# GSB-S02-V00-Microcontroller.net
KiCad netlist of a schematic drawn in Altium Designer
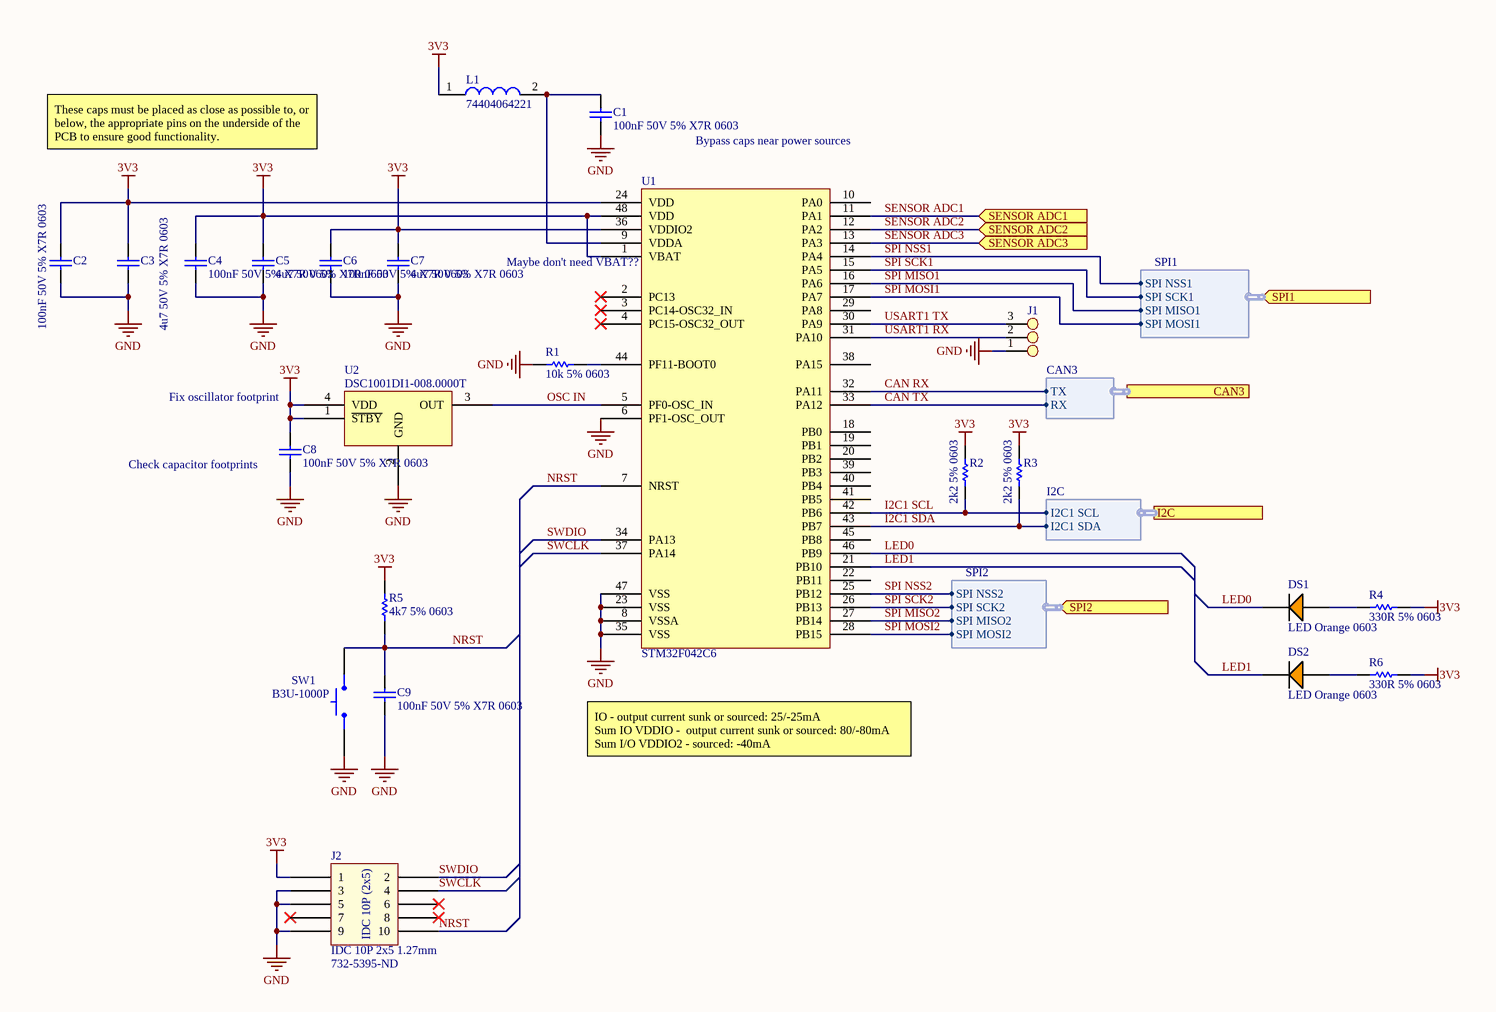
[diagram p0: GSB-S02-V00-Microcontroller.SchDoc]

(export (version "E")
  (design (tool "Eeschema 10.0.6"))
  (components
    (comp (ref "C1")
      (value "100nF 50V 5% X7R 0603")
      (footprint "Cap_Ceramic_0603")
      (description "Capacitor, Ceramic, SMD, 100nF, 50V, 5%, X7R, 0603")
      (libsource (lib "StandardCapacitors") (part "100nF 50V 5% X7R 0603"))
    )
    (comp (ref "C2")
      (value "100nF 50V 5% X7R 0603")
      (footprint "Cap_Ceramic_0603")
      (description "Capacitor, Ceramic, SMD, 100nF, 50V, 5%, X7R, 0603")
      (libsource (lib "StandardCapacitors") (part "100nF 50V 5% X7R 0603"))
    )
    (comp (ref "C3")
      (value "4u7 50V 5% X7R 0603")
      (footprint "Cap_Ceramic_0603")
      (description "Capacitor, Ceramic, SMD, 4u7, 50V, 5%, X7R, 0603")
      (libsource (lib "StandardCapacitors") (part "4u7 50V 5% X7R 0603"))
    )
    (comp (ref "C4")
      (value "100nF 50V 5% X7R 0603")
      (footprint "Cap_Ceramic_0603")
      (description "Capacitor, Ceramic, SMD, 100nF, 50V, 5%, X7R, 0603")
      (libsource (lib "StandardCapacitors") (part "100nF 50V 5% X7R 0603"))
    )
    (comp (ref "C5")
      (value "4u7 50V 5% X7R 0603")
      (footprint "Cap_Ceramic_0603")
      (description "Capacitor, Ceramic, SMD, 4u7, 50V, 5%, X7R, 0603")
      (libsource (lib "StandardCapacitors") (part "4u7 50V 5% X7R 0603"))
    )
    (comp (ref "C6")
      (value "100nF 50V 5% X7R 0603")
      (footprint "Cap_Ceramic_0603")
      (description "Capacitor, Ceramic, SMD, 100nF, 50V, 5%, X7R, 0603")
      (libsource (lib "StandardCapacitors") (part "100nF 50V 5% X7R 0603"))
    )
    (comp (ref "C7")
      (value "4u7 50V 5% X7R 0603")
      (footprint "Cap_Ceramic_0603")
      (description "Capacitor, Ceramic, SMD, 4u7, 50V, 5%, X7R, 0603")
      (libsource (lib "StandardCapacitors") (part "4u7 50V 5% X7R 0603"))
    )
    (comp (ref "C8")
      (value "100nF 50V 5% X7R 0603")
      (footprint "Cap_Ceramic_0603")
      (description "Capacitor, Ceramic, SMD, 100nF, 50V, 5%, X7R, 0603")
      (libsource (lib "StandardCapacitors") (part "100nF 50V 5% X7R 0603"))
    )
    (comp (ref "C9")
      (value "100nF 50V 5% X7R 0603")
      (footprint "Cap_Ceramic_0603")
      (description "Capacitor, Ceramic, SMD, 100nF, 50V, 5%, X7R, 0603")
      (libsource (lib "StandardCapacitors") (part "100nF 50V 5% X7R 0603"))
    )
    (comp (ref "DS1")
      (value "LED Orange 0603")
      (footprint "LED ORANGE 0603")
      (libsource (lib "QUTMS_LEDLibrary") (part "LED Orange 0603"))
    )
    (comp (ref "DS2")
      (value "LED Orange 0603")
      (footprint "LED ORANGE 0603")
      (libsource (lib "QUTMS_LEDLibrary") (part "LED Orange 0603"))
    )
    (comp (ref "J1")
      (value "Jumper 3Way Pins")
      (footprint "Jumper_3Way_Pin")
      (description "Jumper 3Way Side Pins")
      (libsource (lib "QUTMS_JumperLibrary") (part "Jumper 3Way Side Pins"))
    )
    (comp (ref "J2")
      (value "IDC 10P 2x5 1.27mm")
      (footprint "IDC 1.27MM 10P")
      (libsource (lib "IDCConnectors") (part "IDC 10P 2x5 1.27mm"))
    )
    (comp (ref "L1")
      (value "74404064221")
      (footprint "Inductor_6x6mm")
      (description "FIXED IND 220UH 660MA 850 MOHM")
      (libsource (lib "QUTMS_InductorLibrary") (part "74404064221"))
    )
    (comp (ref "R1")
      (value "10k 5% 0603")
      (footprint "Res_ThinFilm_0603")
      (description "Resistor, SMD, 10k, 0.1W, 5%, 0603")
      (libsource (lib "StandardResistors") (part "10k 5% 0603"))
    )
    (comp (ref "R2")
      (value "2k2 5% 0603")
      (footprint "Res_ThinFilm_0603")
      (description "Resistor, SMD, 2k2, 0.1W, 5%, 0603")
      (libsource (lib "StandardResistors") (part "2k2 5% 0603"))
    )
    (comp (ref "R3")
      (value "2k2 5% 0603")
      (footprint "Res_ThinFilm_0603")
      (description "Resistor, SMD, 2k2, 0.1W, 5%, 0603")
      (libsource (lib "StandardResistors") (part "2k2 5% 0603"))
    )
    (comp (ref "R4")
      (value "330R 5% 0603")
      (footprint "Res_ThinFilm_0603")
      (description "Resistor, SMD, 330R, 0.1W, 5%, 0603")
      (libsource (lib "StandardResistors") (part "330R 5% 0603"))
    )
    (comp (ref "R5")
      (value "4k7 5% 0603")
      (footprint "Res_ThinFilm_0603")
      (description "Resistor, SMD, 4k7, 0.1W, 5%, 0603")
      (libsource (lib "StandardResistors") (part "4k7 5% 0603"))
    )
    (comp (ref "R6")
      (value "330R 5% 0603")
      (footprint "Res_ThinFilm_0603")
      (description "Resistor, SMD, 330R, 0.1W, 5%, 0603")
      (libsource (lib "StandardResistors") (part "330R 5% 0603"))
    )
    (comp (ref "SW1")
      (value "B3U-1000P")
      (footprint "BTN B3U-1000P")
      (description "Omron B3U-1000P Ultra Miniture Switch")
      (libsource (lib "QUTMS_SwitchLibrary") (part "BTN B3U-1000P"))
    )
    (comp (ref "U1")
      (value "STM32F042C6")
      (footprint "STM32F042C6")
      (description "ARM® Cortex®-M0 STM32F0 Microcontroller IC 32-Bit 48MHz 32KB (32K x 8) FLASH 48-LQFP (7x7)")
      (libsource (lib "QUTMS_STM32Library") (part "STM32F042C6"))
    )
    (comp (ref "U2")
      (value "DSC1001DI1-008.0000T")
      (footprint "DSC1001DI1-008.0000TCT-ND")
      (description "8MHz XO (Standard) CMOS Oscillator 1.8 ~ 3.3V Standby (Power Down) 4-SMD, No Lead")
      (libsource (lib "QUTMS_CrystalLibrary") (part "DSC1001DI1-008.0000T"))
    )
  )
  (nets
    (net (code "5") (name "/CAN RX") (class "Default")
      (node (ref "U1") (pin "32") (pinfunction "PA11_32") (pintype "passive"))
    )
    (net (code "6") (name "/CAN TX") (class "Default")
      (node (ref "U1") (pin "33") (pinfunction "PA12_33") (pintype "passive"))
    )
    (net (code "7") (name "/I2C1 SCL") (class "Default")
      (node (ref "R2") (pin "1") (pinfunction "1_1") (pintype "passive"))
      (node (ref "U1") (pin "42") (pinfunction "PB6_42") (pintype "passive"))
    )
    (net (code "8") (name "/I2C1 SDA") (class "Default")
      (node (ref "R3") (pin "1") (pinfunction "1_1") (pintype "passive"))
      (node (ref "U1") (pin "43") (pinfunction "PB7_43") (pintype "passive"))
    )
    (net (code "9") (name "/LED0") (class "Default")
      (node (ref "DS1") (pin "2") (pinfunction "C_2") (pintype "passive"))
      (node (ref "U1") (pin "46") (pinfunction "PB9_46") (pintype "passive"))
    )
    (net (code "10") (name "/LED1") (class "Default")
      (node (ref "DS2") (pin "2") (pinfunction "C_2") (pintype "passive"))
      (node (ref "U1") (pin "21") (pinfunction "PB10_21") (pintype "passive"))
    )
    (net (code "11") (name "/NRST") (class "Default")
      (node (ref "C9") (pin "2") (pinfunction "2_2") (pintype "passive"))
      (node (ref "J2") (pin "10") (pinfunction "10_10") (pintype "passive"))
      (node (ref "R5") (pin "1") (pinfunction "1_1") (pintype "passive"))
      (node (ref "SW1") (pin "2") (pinfunction "2_2") (pintype "passive"))
      (node (ref "U1") (pin "7") (pinfunction "NRST_7") (pintype "passive"))
    )
    (net (code "12") (name "/OSC IN") (class "Default")
      (node (ref "U1") (pin "5") (pinfunction "PF0-OSC_IN_5") (pintype "passive"))
      (node (ref "U2") (pin "3") (pinfunction "OUT_3") (pintype "passive"))
    )
    (net (code "13") (name "/SENSOR ADC1") (class "Default")
      (node (ref "U1") (pin "11") (pinfunction "PA1_11") (pintype "passive"))
    )
    (net (code "14") (name "/SENSOR ADC2") (class "Default")
      (node (ref "U1") (pin "12") (pinfunction "PA2_12") (pintype "passive"))
    )
    (net (code "15") (name "/SENSOR ADC3") (class "Default")
      (node (ref "U1") (pin "13") (pinfunction "PA3_13") (pintype "passive"))
    )
    (net (code "16") (name "/SPI MISO1") (class "Default")
      (node (ref "U1") (pin "16") (pinfunction "PA6_16") (pintype "passive"))
    )
    (net (code "17") (name "/SPI MISO2") (class "Default")
      (node (ref "U1") (pin "27") (pinfunction "PB14_27") (pintype "passive"))
    )
    (net (code "18") (name "/SPI MOSI1") (class "Default")
      (node (ref "U1") (pin "17") (pinfunction "PA7_17") (pintype "passive"))
    )
    (net (code "19") (name "/SPI MOSI2") (class "Default")
      (node (ref "U1") (pin "28") (pinfunction "PB15_28") (pintype "passive"))
    )
    (net (code "20") (name "/SPI NSS1") (class "Default")
      (node (ref "U1") (pin "14") (pinfunction "PA4_14") (pintype "passive"))
    )
    (net (code "21") (name "/SPI NSS2") (class "Default")
      (node (ref "U1") (pin "25") (pinfunction "PB12_25") (pintype "passive"))
    )
    (net (code "22") (name "/SPI SCK1") (class "Default")
      (node (ref "U1") (pin "15") (pinfunction "PA5_15") (pintype "passive"))
    )
    (net (code "23") (name "/SPI SCK2") (class "Default")
      (node (ref "U1") (pin "26") (pinfunction "PB13_26") (pintype "passive"))
    )
    (net (code "24") (name "/SWCLK") (class "Default")
      (node (ref "J2") (pin "4") (pinfunction "4_4") (pintype "passive"))
      (node (ref "U1") (pin "37") (pinfunction "PA14_37") (pintype "passive"))
    )
    (net (code "25") (name "/SWDIO") (class "Default")
      (node (ref "J2") (pin "2") (pinfunction "2_2") (pintype "passive"))
      (node (ref "U1") (pin "34") (pinfunction "PA13_34") (pintype "passive"))
    )
    (net (code "26") (name "/USART1 RX") (class "Default")
      (node (ref "J1") (pin "2") (pinfunction "2_2") (pintype "passive"))
      (node (ref "U1") (pin "31") (pinfunction "PA10_31") (pintype "passive"))
    )
    (net (code "27") (name "/USART1 TX") (class "Default")
      (node (ref "J1") (pin "3") (pinfunction "3_3") (pintype "passive"))
      (node (ref "U1") (pin "30") (pinfunction "PA9_30") (pintype "passive"))
    )
    (net (code "32") (name "3V3") (class "Default")
      (node (ref "C2") (pin "2") (pinfunction "2_2") (pintype "passive"))
      (node (ref "C3") (pin "2") (pinfunction "2_2") (pintype "passive"))
      (node (ref "C4") (pin "2") (pinfunction "2_2") (pintype "passive"))
      (node (ref "C5") (pin "2") (pinfunction "2_2") (pintype "passive"))
      (node (ref "C6") (pin "2") (pinfunction "2_2") (pintype "passive"))
      (node (ref "C7") (pin "2") (pinfunction "2_2") (pintype "passive"))
      (node (ref "C8") (pin "2") (pinfunction "2_2") (pintype "passive"))
      (node (ref "J2") (pin "1") (pinfunction "1_1") (pintype "passive"))
      (node (ref "L1") (pin "1") (pinfunction "1_1") (pintype "passive"))
      (node (ref "R2") (pin "2") (pinfunction "2_2") (pintype "passive"))
      (node (ref "R3") (pin "2") (pinfunction "2_2") (pintype "passive"))
      (node (ref "R4") (pin "2") (pinfunction "2_2") (pintype "passive"))
      (node (ref "R5") (pin "2") (pinfunction "2_2") (pintype "passive"))
      (node (ref "R6") (pin "2") (pinfunction "2_2") (pintype "passive"))
      (node (ref "U1") (pin "1") (pinfunction "VBAT_1") (pintype "passive"))
      (node (ref "U1") (pin "24") (pinfunction "VDD_24") (pintype "passive"))
      (node (ref "U1") (pin "36") (pinfunction "VDDIO2_36") (pintype "passive"))
      (node (ref "U1") (pin "48") (pinfunction "VDD_48") (pintype "passive"))
      (node (ref "U2") (pin "1") (pinfunction "~{STBY}_1") (pintype "passive"))
      (node (ref "U2") (pin "4") (pinfunction "VDD_4") (pintype "passive"))
    )
    (net (code "33") (name "GND") (class "Default")
      (node (ref "C1") (pin "1") (pinfunction "1_1") (pintype "passive"))
      (node (ref "C2") (pin "1") (pinfunction "1_1") (pintype "passive"))
      (node (ref "C3") (pin "1") (pinfunction "1_1") (pintype "passive"))
      (node (ref "C4") (pin "1") (pinfunction "1_1") (pintype "passive"))
      (node (ref "C5") (pin "1") (pinfunction "1_1") (pintype "passive"))
      (node (ref "C6") (pin "1") (pinfunction "1_1") (pintype "passive"))
      (node (ref "C7") (pin "1") (pinfunction "1_1") (pintype "passive"))
      (node (ref "C8") (pin "1") (pinfunction "1_1") (pintype "passive"))
      (node (ref "C9") (pin "1") (pinfunction "1_1") (pintype "passive"))
      (node (ref "J1") (pin "1") (pinfunction "1_1") (pintype "passive"))
      (node (ref "J2") (pin "3") (pinfunction "3_3") (pintype "passive"))
      (node (ref "J2") (pin "5") (pinfunction "5_5") (pintype "passive"))
      (node (ref "J2") (pin "9") (pinfunction "9_9") (pintype "passive"))
      (node (ref "R1") (pin "1") (pinfunction "1_1") (pintype "passive"))
      (node (ref "SW1") (pin "1") (pinfunction "1_1") (pintype "passive"))
      (node (ref "U1") (pin "23") (pinfunction "VSS_23") (pintype "passive"))
      (node (ref "U1") (pin "35") (pinfunction "VSS_35") (pintype "passive"))
      (node (ref "U1") (pin "47") (pinfunction "VSS_47") (pintype "passive"))
      (node (ref "U1") (pin "6") (pinfunction "PF1-OSC_OUT_6") (pintype "passive"))
      (node (ref "U1") (pin "8") (pinfunction "VSSA_8") (pintype "passive"))
      (node (ref "U2") (pin "2") (pinfunction "GND_2") (pintype "passive"))
    )
    (net (code "34") (name "Net-(DS1-A)") (class "Default")
      (node (ref "DS1") (pin "1") (pinfunction "A_1") (pintype "passive"))
      (node (ref "R4") (pin "1") (pinfunction "1_1") (pintype "passive"))
    )
    (net (code "35") (name "Net-(DS2-A)") (class "Default")
      (node (ref "DS2") (pin "1") (pinfunction "A_1") (pintype "passive"))
      (node (ref "R6") (pin "1") (pinfunction "1_1") (pintype "passive"))
    )
    (net (code "36") (name "Net-(U1-PF11-BOOT0)") (class "Default")
      (node (ref "R1") (pin "2") (pinfunction "2_2") (pintype "passive"))
      (node (ref "U1") (pin "44") (pinfunction "PF11-BOOT0_44") (pintype "passive"))
    )
    (net (code "37") (name "Net-(U1-VDDA)") (class "Default")
      (node (ref "C1") (pin "2") (pinfunction "2_2") (pintype "passive"))
      (node (ref "L1") (pin "2") (pinfunction "2_2") (pintype "passive"))
      (node (ref "U1") (pin "9") (pinfunction "VDDA_9") (pintype "passive"))
    )
    (net (code "38") (name "unconnected-(J2-Pad6)") (class "Default")
      (node (ref "J2") (pin "6") (pinfunction "6_6") (pintype "passive+no_connect"))
    )
    (net (code "39") (name "unconnected-(J2-Pad7)") (class "Default")
      (node (ref "J2") (pin "7") (pinfunction "7_7") (pintype "passive+no_connect"))
    )
    (net (code "40") (name "unconnected-(J2-Pad8)") (class "Default")
      (node (ref "J2") (pin "8") (pinfunction "8_8") (pintype "passive+no_connect"))
    )
    (net (code "41") (name "unconnected-(U1-PA0-Pad10)") (class "Default")
      (node (ref "U1") (pin "10") (pinfunction "PA0_10") (pintype "passive"))
    )
    (net (code "42") (name "unconnected-(U1-PA8-Pad29)") (class "Default")
      (node (ref "U1") (pin "29") (pinfunction "PA8_29") (pintype "passive"))
    )
    (net (code "43") (name "unconnected-(U1-PA15-Pad38)") (class "Default")
      (node (ref "U1") (pin "38") (pinfunction "PA15_38") (pintype "passive"))
    )
    (net (code "44") (name "unconnected-(U1-PB0-Pad18)") (class "Default")
      (node (ref "U1") (pin "18") (pinfunction "PB0_18") (pintype "passive"))
    )
    (net (code "45") (name "unconnected-(U1-PB1-Pad19)") (class "Default")
      (node (ref "U1") (pin "19") (pinfunction "PB1_19") (pintype "passive"))
    )
    (net (code "46") (name "unconnected-(U1-PB2-Pad20)") (class "Default")
      (node (ref "U1") (pin "20") (pinfunction "PB2_20") (pintype "passive"))
    )
    (net (code "47") (name "unconnected-(U1-PB3-Pad39)") (class "Default")
      (node (ref "U1") (pin "39") (pinfunction "PB3_39") (pintype "passive"))
    )
    (net (code "48") (name "unconnected-(U1-PB4-Pad40)") (class "Default")
      (node (ref "U1") (pin "40") (pinfunction "PB4_40") (pintype "passive"))
    )
    (net (code "49") (name "unconnected-(U1-PB5-Pad41)") (class "Default")
      (node (ref "U1") (pin "41") (pinfunction "PB5_41") (pintype "passive"))
    )
    (net (code "50") (name "unconnected-(U1-PB8-Pad45)") (class "Default")
      (node (ref "U1") (pin "45") (pinfunction "PB8_45") (pintype "passive"))
    )
    (net (code "51") (name "unconnected-(U1-PB11-Pad22)") (class "Default")
      (node (ref "U1") (pin "22") (pinfunction "PB11_22") (pintype "passive"))
    )
    (net (code "52") (name "unconnected-(U1-PC13-Pad2)") (class "Default")
      (node (ref "U1") (pin "2") (pinfunction "PC13_2") (pintype "passive+no_connect"))
    )
    (net (code "53") (name "unconnected-(U1-PC14-OSC32_IN-Pad3)") (class "Default")
      (node (ref "U1") (pin "3") (pinfunction "PC14-OSC32_IN_3") (pintype "passive+no_connect"))
    )
    (net (code "54") (name "unconnected-(U1-PC15-OSC32_OUT-Pad4)") (class "Default")
      (node (ref "U1") (pin "4") (pinfunction "PC15-OSC32_OUT_4") (pintype "passive+no_connect"))
    )
  )
)
